# POWER.net
KiCad netlist of a schematic drawn in Altium Designer
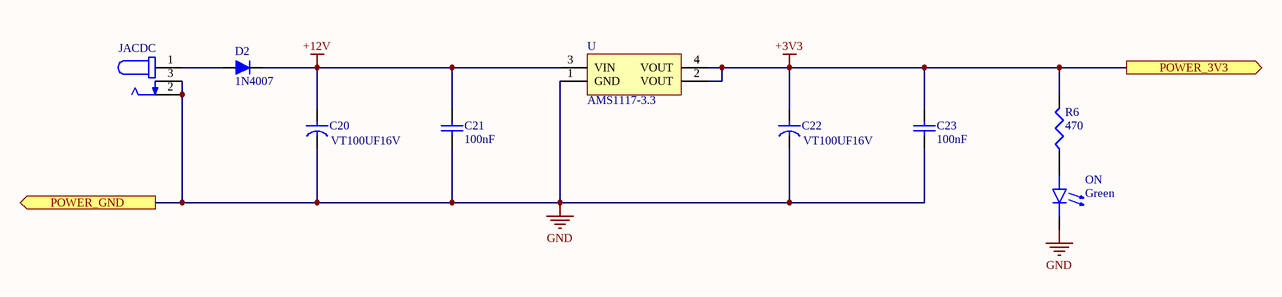
[diagram p0: POWER.SchDoc]

(export (version "E")
  (design (tool "Eeschema 10.0.6"))
  (components
    (comp (ref "C20")
      (value "VT100UF16V")
      (footprint "SMD,D6.3xL5.4mm")
      (description "100uF 16V 60mA@120Hz ±20% SMD,D6.3xL5.4mm  Aluminum Electrolytic Capacitors - SMD ROHS")
      (fields (field (name "JLCPCB PART #") "C5246579"))
      (libsource (lib "Ho Chi Minh City University of Technology") (part "Capacitor"))
    )
    (comp (ref "C21")
      (value "100nF")
      (footprint "CAPC0805(2012)145_L")
      (description "Chip Capacitor, 100nF +/-40%, 16V, 0805, Thickness 1.45 mm")
      (fields (field (name "TOLERANCE") "5%"))
      (libsource (lib "Ho Chi Minh City University of Technology") (part "CAP-NP-2"))
    )
    (comp (ref "C22")
      (value "VT100UF16V")
      (footprint "SMD,D6.3xL5.4mm")
      (description "100uF 16V 60mA@120Hz ±20% SMD,D6.3xL5.4mm  Aluminum Electrolytic Capacitors - SMD ROHS")
      (fields (field (name "JLCPCB PART #") "C5246579"))
      (libsource (lib "Ho Chi Minh City University of Technology") (part "Capacitor"))
    )
    (comp (ref "C23")
      (value "100nF")
      (footprint "CAPC0805(2012)145_L")
      (description "Chip Capacitor, 100nF +/-40%, 16V, 0805, Thickness 1.45 mm")
      (fields (field (name "TOLERANCE") "5%"))
      (libsource (lib "Ho Chi Minh City University of Technology") (part "CAP-NP-2"))
    )
    (comp (ref "D2")
      (value "1N4007")
      (footprint "1N4007")
      (fields (field (name "JLCPCB PART #") "C95872"))
      (libsource (lib "Ho Chi Minh City University of Technology") (part "diode"))
    )
    (comp (ref "JACDC")
      (value "DCJ200-10-A-XX-K_REVA")
      (footprint "GCT_DCJ200-10-A-XX-K_REVA")
      (description "Power Barrel Connector Jack 2.05mm ID (0.081), 5.50mm OD (0.217) Through Hole, Right Angle")
      (fields (field (name "MP") "DCJ200-10-A-K1-K") (field (name "MF") "Global Connector Technology"))
      (libsource (lib "Ho Chi Minh City University of Technology") (part "DCJ200-10-A-XX-K_REVA"))
    )
    (comp (ref "ON")
      (value "Green")
      (footprint "0805 (2012 Metric) Green")
      (description "Oreki")
      (fields (field (name "JLCPCB PART #") "C389524"))
      (libsource (lib "Ho Chi Minh City University of Technology") (part "Symbol"))
    )
    (comp (ref "R6")
      (value "470")
      (footprint "0805 (2012 Metric)")
      (description "Oreki")
      (fields (field (name "Comment") "220"))
      (libsource (lib "Ho Chi Minh City University of Technology") (part "RES-2"))
    )
    (comp (ref "U")
      (value "AMS1117-3.3")
      (footprint "SOT229P700X180-4N")
      (description "Oreki")
      (fields (field (name "JLCPCB PART #") "C6186"))
      (libsource (lib "Ho Chi Minh City University of Technology") (part "AMS1117"))
    )
  )
  (nets
    (net (code "1") (name "+3V3") (class "Default")
      (node (ref "C22") (pin "1") (pinfunction "1_1") (pintype "passive"))
      (node (ref "C23") (pin "2") (pinfunction "2_2") (pintype "passive"))
      (node (ref "R6") (pin "2") (pinfunction "2_2") (pintype "passive"))
      (node (ref "U") (pin "2") (pinfunction "VOUT_2") (pintype "power_in"))
      (node (ref "U") (pin "4") (pinfunction "VOUT_4") (pintype "power_in"))
    )
    (net (code "2") (name "+12V") (class "Default")
      (node (ref "C20") (pin "1") (pinfunction "1_1") (pintype "passive"))
      (node (ref "C21") (pin "2") (pinfunction "2_2") (pintype "passive"))
      (node (ref "D2") (pin "1") (pinfunction "1_1") (pintype "passive"))
      (node (ref "U") (pin "3") (pinfunction "VIN_3") (pintype "power_in"))
    )
    (net (code "3") (name "GND") (class "Default")
      (node (ref "C20") (pin "2") (pinfunction "2_2") (pintype "passive"))
      (node (ref "C21") (pin "1") (pinfunction "1_1") (pintype "passive"))
      (node (ref "C22") (pin "2") (pinfunction "2_2") (pintype "passive"))
      (node (ref "C23") (pin "1") (pinfunction "1_1") (pintype "passive"))
      (node (ref "JACDC") (pin "2") (pinfunction "2_2") (pintype "passive"))
      (node (ref "JACDC") (pin "3") (pinfunction "3_3") (pintype "passive"))
      (node (ref "ON") (pin "1") (pinfunction "K_1") (pintype "passive"))
      (node (ref "U") (pin "1") (pinfunction "GND_1") (pintype "power_in"))
    )
    (net (code "4") (name "Net-(D2-Pad2)") (class "Default")
      (node (ref "D2") (pin "2") (pinfunction "2_2") (pintype "passive"))
      (node (ref "JACDC") (pin "1") (pinfunction "1_1") (pintype "passive"))
    )
    (net (code "5") (name "Net-(ON-A)") (class "Default")
      (node (ref "ON") (pin "2") (pinfunction "A_2") (pintype "passive"))
      (node (ref "R6") (pin "1") (pinfunction "1_1") (pintype "passive"))
    )
  )
)
